# DAC_adacus_sch.net
KiCad netlist of a schematic drawn in Altium Designer
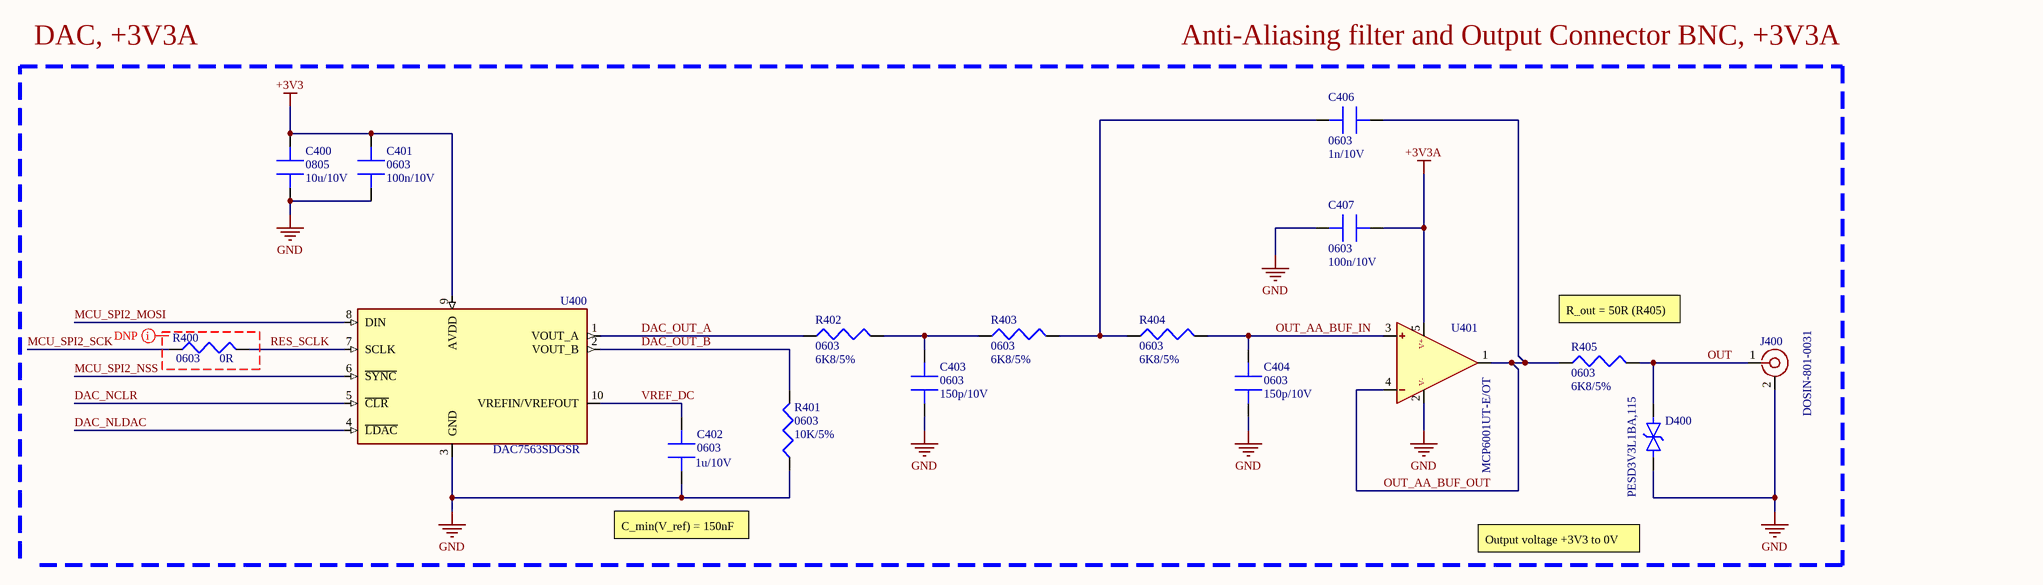
[diagram p0: DAC_adacus_sch.SchDoc]

(export (version "E")
  (design (tool "Eeschema 10.0.6"))
  (components
    (comp (ref "C400")
      (value "10u/10V")
      (footprint "[0805] CAPC2012X09M [A - LD]")
      (description "Standard Capacitor")
      (fields (field (name "PACKAGE") "0805") (field (name "Comment") "Capacitor"))
      (libsource (lib "adacus_schlib") (part "Capacitor"))
    )
    (comp (ref "C401")
      (value "100n/10V")
      (footprint "[0603] CAPC1608X10M [A-LD]")
      (description "Standard Capacitor")
      (fields (field (name "PACKAGE") "0603") (field (name "Comment") "Capacitor"))
      (libsource (lib "adacus_schlib") (part "Capacitor"))
    )
    (comp (ref "C402")
      (value "1u/10V")
      (footprint "[0603] CAPC1608X10M [A-LD]")
      (description "Standard Capacitor")
      (fields (field (name "PACKAGE") "0603") (field (name "Comment") "Capacitor"))
      (libsource (lib "adacus_schlib") (part "Capacitor"))
    )
    (comp (ref "C403")
      (value "150p/10V")
      (footprint "[0603] CAPC1608X10M [A-LD]")
      (description "Standard Capacitor")
      (fields (field (name "PACKAGE") "0603") (field (name "Comment") "Capacitor"))
      (libsource (lib "adacus_schlib") (part "Capacitor"))
    )
    (comp (ref "C404")
      (value "150p/10V")
      (footprint "[0603] CAPC1608X10M [A-LD]")
      (description "Standard Capacitor")
      (fields (field (name "PACKAGE") "0603") (field (name "Comment") "Capacitor"))
      (libsource (lib "adacus_schlib") (part "Capacitor"))
    )
    (comp (ref "C406")
      (value "1n/10V")
      (footprint "[0603] CAPC1608X10M [A-LD]")
      (description "Standard Capacitor")
      (fields (field (name "PACKAGE") "0603") (field (name "Comment") "Capacitor"))
      (libsource (lib "adacus_schlib") (part "Capacitor"))
    )
    (comp (ref "C407")
      (value "100n/10V")
      (footprint "[0603] CAPC1608X10M [A-LD]")
      (description "Standard Capacitor")
      (fields (field (name "PACKAGE") "0603") (field (name "Comment") "Capacitor"))
      (libsource (lib "adacus_schlib") (part "Capacitor"))
    )
    (comp (ref "D400")
      (value "PESD3V3L1BA,115")
      (footprint "SODFL250X110-2M")
      (description "ESD Suppressors / TVS Diodes PESD3V3L1BA/SOD323/SOD2")
      (libsource (lib "adacus_schlib") (part "PESD3V3L1BA,115"))
    )
    (comp (ref "J400")
      (value "DOSIN-801-0031")
      (footprint "DOSIN8010031")
      (description "BNC Board Edge Bend 9.6mm Plugin RF Connectors / Coaxial Connectors")
      (libsource (lib "adacus_schlib") (part "BNC Connector"))
    )
    (comp (ref "R400")
      (value "0R")
      (footprint "[0603] RESC1608X06M [A-LD]")
      (description "Standard Resistor")
      (fields (field (name "PACKAGE") "0603") (field (name "Comment") "Resistor"))
      (libsource (lib "adacus_schlib") (part "Resistor"))
    )
    (comp (ref "R401")
      (value "10K/5%")
      (footprint "[0603] RESC1608X06M [A-LD]")
      (description "Standard Resistor")
      (fields (field (name "PACKAGE") "0603") (field (name "Comment") "Resistor"))
      (libsource (lib "adacus_schlib") (part "Resistor"))
    )
    (comp (ref "R402")
      (value "6K8/5%")
      (footprint "[0603] RESC1608X06M [A-LD]")
      (description "Standard Resistor")
      (fields (field (name "PACKAGE") "0603") (field (name "Comment") "Resistor"))
      (libsource (lib "adacus_schlib") (part "Resistor"))
    )
    (comp (ref "R403")
      (value "6K8/5%")
      (footprint "[0603] RESC1608X06M [A-LD]")
      (description "Standard Resistor")
      (fields (field (name "PACKAGE") "0603") (field (name "Comment") "Resistor"))
      (libsource (lib "adacus_schlib") (part "Resistor"))
    )
    (comp (ref "R404")
      (value "6K8/5%")
      (footprint "[0603] RESC1608X06M [A-LD]")
      (description "Standard Resistor")
      (fields (field (name "PACKAGE") "0603") (field (name "Comment") "Resistor"))
      (libsource (lib "adacus_schlib") (part "Resistor"))
    )
    (comp (ref "R405")
      (value "6K8/5%")
      (footprint "[0603] RESC1608X06M [A-LD]")
      (description "Standard Resistor")
      (fields (field (name "PACKAGE") "0603") (field (name "Comment") "Resistor"))
      (libsource (lib "adacus_schlib") (part "Resistor"))
    )
    (comp (ref "U400")
      (value "DAC7563SDGSR")
      (footprint "TSSOP50P490X110-10M")
      (description "Digital to Analog Converters - DAC 12B,Dual,Lo Pwr Ultra-Lo Glitch DAC")
      (libsource (lib "adacus_schlib") (part "DAC7563SDGSR"))
    )
    (comp (ref "U401")
      (value "MCP6001UT-E/OT")
      (footprint "SOT95P270X145-5M")
      (description "Operational Amplifiers - Op Amps Single 1.8V 1MHz")
      (libsource (lib "adacus_schlib") (part "MCP6001UT-E/OT"))
    )
  )
  (nets
    (net (code "1") (name "+3V3") (class "Default")
      (node (ref "C400") (pin "2") (pinfunction "2_2") (pintype "passive"))
      (node (ref "C401") (pin "2") (pinfunction "2_2") (pintype "passive"))
      (node (ref "U400") (pin "9") (pinfunction "AVDD_9") (pintype "input"))
    )
    (net (code "2") (name "+3V3A") (class "Default")
      (node (ref "C407") (pin "1") (pinfunction "1_1") (pintype "passive"))
      (node (ref "U401") (pin "5") (pinfunction "VDD_5") (pintype "passive"))
    )
    (net (code "3") (name "/DAC_NCLR") (class "Default")
      (node (ref "U400") (pin "5") (pinfunction "~{CLR}_5") (pintype "input"))
    )
    (net (code "4") (name "/DAC_NLDAC") (class "Default")
      (node (ref "U400") (pin "4") (pinfunction "~{LDAC}_4") (pintype "input"))
    )
    (net (code "5") (name "/DAC_OUT_A") (class "Default")
      (node (ref "R402") (pin "2") (pinfunction "2_2") (pintype "passive"))
      (node (ref "U400") (pin "1") (pinfunction "VOUT_A_1") (pintype "output"))
    )
    (net (code "6") (name "/DAC_OUT_B") (class "Default")
      (node (ref "R401") (pin "1") (pinfunction "1_1") (pintype "passive"))
      (node (ref "U400") (pin "2") (pinfunction "VOUT_B_2") (pintype "output"))
    )
    (net (code "7") (name "/MCU_SPI2_MOSI") (class "Default")
      (node (ref "U400") (pin "8") (pinfunction "DIN_8") (pintype "input"))
    )
    (net (code "8") (name "/MCU_SPI2_NSS") (class "Default")
      (node (ref "U400") (pin "6") (pinfunction "~{SYNC}_6") (pintype "input"))
    )
    (net (code "9") (name "/MCU_SPI2_SCK") (class "Default")
      (node (ref "R400") (pin "2") (pinfunction "2_2") (pintype "passive"))
    )
    (net (code "10") (name "/OUT") (class "Default")
      (node (ref "D400") (pin "2") (pinfunction "2_2") (pintype "passive"))
      (node (ref "J400") (pin "1") (pinfunction "1_1") (pintype "passive"))
      (node (ref "R405") (pin "1") (pinfunction "1_1") (pintype "passive"))
    )
    (net (code "11") (name "/OUT_AA_BUF_IN") (class "Default")
      (node (ref "C404") (pin "2") (pinfunction "2_2") (pintype "passive"))
      (node (ref "R404") (pin "1") (pinfunction "1_1") (pintype "passive"))
      (node (ref "U401") (pin "3") (pinfunction "+_3") (pintype "passive"))
    )
    (net (code "12") (name "/OUT_AA_BUF_OUT") (class "Default")
      (node (ref "C406") (pin "1") (pinfunction "1_1") (pintype "passive"))
      (node (ref "R405") (pin "2") (pinfunction "2_2") (pintype "passive"))
      (node (ref "U401") (pin "1") (pinfunction "OUT_1") (pintype "passive"))
      (node (ref "U401") (pin "4") (pinfunction "-_4") (pintype "passive"))
    )
    (net (code "13") (name "/RES_SCLK") (class "Default")
      (node (ref "R400") (pin "1") (pinfunction "1_1") (pintype "passive"))
      (node (ref "U400") (pin "7") (pinfunction "SCLK_7") (pintype "input"))
    )
    (net (code "14") (name "/VREF_DC") (class "Default")
      (node (ref "C402") (pin "2") (pinfunction "2_2") (pintype "passive"))
      (node (ref "U400") (pin "10") (pinfunction "VREFIN/VREFOUT_10") (pintype "bidirectional"))
    )
    (net (code "15") (name "GND") (class "Default")
      (node (ref "C400") (pin "1") (pinfunction "1_1") (pintype "passive"))
      (node (ref "C401") (pin "1") (pinfunction "1_1") (pintype "passive"))
      (node (ref "C402") (pin "1") (pinfunction "1_1") (pintype "passive"))
      (node (ref "C403") (pin "1") (pinfunction "1_1") (pintype "passive"))
      (node (ref "C404") (pin "1") (pinfunction "1_1") (pintype "passive"))
      (node (ref "C407") (pin "2") (pinfunction "2_2") (pintype "passive"))
      (node (ref "D400") (pin "1") (pinfunction "1_1") (pintype "passive"))
      (node (ref "J400") (pin "2") (pinfunction "2_2") (pintype "passive"))
      (node (ref "R401") (pin "2") (pinfunction "2_2") (pintype "passive"))
      (node (ref "U400") (pin "3") (pinfunction "GND_3") (pintype "passive"))
      (node (ref "U401") (pin "2") (pinfunction "VSS_2") (pintype "passive"))
    )
    (net (code "16") (name "Net-(C403-Pad2)") (class "Default")
      (node (ref "C403") (pin "2") (pinfunction "2_2") (pintype "passive"))
      (node (ref "R402") (pin "1") (pinfunction "1_1") (pintype "passive"))
      (node (ref "R403") (pin "2") (pinfunction "2_2") (pintype "passive"))
    )
    (net (code "17") (name "Net-(C406-Pad2)") (class "Default")
      (node (ref "C406") (pin "2") (pinfunction "2_2") (pintype "passive"))
      (node (ref "R403") (pin "1") (pinfunction "1_1") (pintype "passive"))
      (node (ref "R404") (pin "2") (pinfunction "2_2") (pintype "passive"))
    )
  )
)
